# STM32F446_Supply.net
KiCad netlist of a schematic drawn in Altium Designer
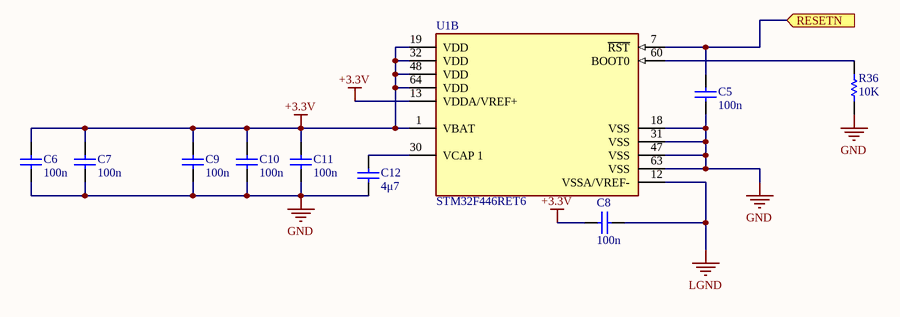
[diagram p0: STM32F446_Supply.SchDoc]

(export (version "E")
  (design (tool "Eeschema 10.0.6"))
  (components
    (comp (ref "C5")
      (value "100n")
      (footprint "CAPC0603(1608)55_N")
      (description "Keramikvielschichtkondensator, SMD, Baureihe MC, ± 10%")
      (fields (field (name "MANUFACTURER") "TDK") (field (name "TOLERANCE") "± 10%"))
      (libsource (lib "Res&Caps") (part "Cap 100n"))
    )
    (comp (ref "C6")
      (value "100n")
      (footprint "CAPC0603(1608)55_N")
      (description "Keramikvielschichtkondensator, SMD, Baureihe MC, ± 10%")
      (fields (field (name "MANUFACTURER") "TDK") (field (name "TOLERANCE") "± 10%"))
      (libsource (lib "Res&Caps") (part "Cap 100n"))
    )
    (comp (ref "C7")
      (value "100n")
      (footprint "CAPC0603(1608)55_N")
      (description "Keramikvielschichtkondensator, SMD, Baureihe MC, ± 10%")
      (fields (field (name "MANUFACTURER") "TDK") (field (name "TOLERANCE") "± 10%"))
      (libsource (lib "Res&Caps") (part "Cap 100n"))
    )
    (comp (ref "C8")
      (value "100n")
      (footprint "CAPC0603(1608)55_N")
      (description "Keramikvielschichtkondensator, SMD, Baureihe MC, ± 10%")
      (fields (field (name "MANUFACTURER") "TDK") (field (name "TOLERANCE") "± 10%"))
      (libsource (lib "Res&Caps") (part "Cap 100n"))
    )
    (comp (ref "C9")
      (value "100n")
      (footprint "CAPC0603(1608)55_N")
      (description "Keramikvielschichtkondensator, SMD, Baureihe MC, ± 10%")
      (fields (field (name "MANUFACTURER") "TDK") (field (name "TOLERANCE") "± 10%"))
      (libsource (lib "Res&Caps") (part "Cap 100n"))
    )
    (comp (ref "C10")
      (value "100n")
      (footprint "CAPC0603(1608)55_N")
      (description "Keramikvielschichtkondensator, SMD, Baureihe MC, ± 10%")
      (fields (field (name "MANUFACTURER") "TDK") (field (name "TOLERANCE") "± 10%"))
      (libsource (lib "Res&Caps") (part "Cap 100n"))
    )
    (comp (ref "C11")
      (value "100n")
      (footprint "CAPC0603(1608)55_N")
      (description "Keramikvielschichtkondensator, SMD, Baureihe MC, ± 10%")
      (fields (field (name "MANUFACTURER") "TDK") (field (name "TOLERANCE") "± 10%"))
      (libsource (lib "Res&Caps") (part "Cap 100n"))
    )
    (comp (ref "C12")
      (value "4μ7")
      (footprint "CAPC0603(1608)55_N")
      (description "Keramikvielschichtkondensator, SMD, Baureihe MC, ± 10%")
      (fields (field (name "MANUFACTURER") "TDK") (field (name "TOLERANCE") "± 10%"))
      (libsource (lib "Res&Caps") (part "Cap 4μ7"))
    )
    (comp (ref "R36")
      (value "10K")
      (footprint "RESC0603(1608)_N")
      (description "Chipwiderstand, SMD, Baureihe MC, 1%")
      (fields (field (name "MANUFACTURER") "Multicomp") (field (name "POWER") "100mW"))
      (libsource (lib "Res&Caps") (part "Res 10K"))
    )
    (comp (ref "U1")
      (value "STM32F446RET6")
      (footprint "FP-LQFP64-5W-MFG")
      (description "IC MCU 32BIT 512KB FLASH 64LQFP")
      (fields
        (field (name "OCTOPART") "https://octopart.com/stm32f446ret6-stmicroelectronics-52642920")
        (field (name "MANUFACTURER") "ST")
      )
      (libsource (lib "Altium Content Vault") (part "ee11adc32c0ab33b933cccf4348c338"))
    )
  )
  (nets
    (net (code "1") (name "+3.3V") (class "Default")
      (node (ref "C10") (pin "2") (pinfunction "2_2") (pintype "passive"))
      (node (ref "C11") (pin "2") (pinfunction "2_2") (pintype "passive"))
      (node (ref "C6") (pin "2") (pinfunction "2_2") (pintype "passive"))
      (node (ref "C7") (pin "2") (pinfunction "2_2") (pintype "passive"))
      (node (ref "C8") (pin "2") (pinfunction "2_2") (pintype "passive"))
      (node (ref "C9") (pin "2") (pinfunction "2_2") (pintype "passive"))
      (node (ref "U1") (pin "1") (pinfunction "VBAT_1") (pintype "power_in"))
      (node (ref "U1") (pin "13") (pinfunction "VDDA/VREF+_13") (pintype "power_in"))
      (node (ref "U1") (pin "19") (pinfunction "VDD_19") (pintype "power_in"))
      (node (ref "U1") (pin "32") (pinfunction "VDD_32") (pintype "power_in"))
      (node (ref "U1") (pin "48") (pinfunction "VDD_48") (pintype "power_in"))
      (node (ref "U1") (pin "64") (pinfunction "VDD_64") (pintype "power_in"))
    )
    (net (code "2") (name "/RESETN") (class "Default")
      (node (ref "C5") (pin "2") (pinfunction "2_2") (pintype "passive"))
      (node (ref "U1") (pin "7") (pinfunction "~{RST}_7") (pintype "input"))
    )
    (net (code "3") (name "GND") (class "Default")
      (node (ref "C10") (pin "1") (pinfunction "1_1") (pintype "passive"))
      (node (ref "C11") (pin "1") (pinfunction "1_1") (pintype "passive"))
      (node (ref "C12") (pin "1") (pinfunction "1_1") (pintype "passive"))
      (node (ref "C5") (pin "1") (pinfunction "1_1") (pintype "passive"))
      (node (ref "C6") (pin "1") (pinfunction "1_1") (pintype "passive"))
      (node (ref "C7") (pin "1") (pinfunction "1_1") (pintype "passive"))
      (node (ref "C9") (pin "1") (pinfunction "1_1") (pintype "passive"))
      (node (ref "R36") (pin "1") (pinfunction "1_1") (pintype "passive"))
      (node (ref "U1") (pin "18") (pinfunction "VSS_18") (pintype "power_in"))
      (node (ref "U1") (pin "31") (pinfunction "VSS_31") (pintype "power_in"))
      (node (ref "U1") (pin "47") (pinfunction "VSS_47") (pintype "power_in"))
      (node (ref "U1") (pin "63") (pinfunction "VSS_63") (pintype "power_in"))
    )
    (net (code "4") (name "LGND") (class "Default")
      (node (ref "C8") (pin "1") (pinfunction "1_1") (pintype "passive"))
      (node (ref "U1") (pin "12") (pinfunction "VSSA/VREF-_12") (pintype "power_in"))
    )
    (net (code "5") (name "Net-(U1B-BOOT0)") (class "Default")
      (node (ref "R36") (pin "2") (pinfunction "2_2") (pintype "passive"))
      (node (ref "U1") (pin "60") (pinfunction "BOOT0_60") (pintype "input"))
    )
    (net (code "6") (name "Net-(U1B-VCAP_1)") (class "Default")
      (node (ref "C12") (pin "2") (pinfunction "2_2") (pintype "passive"))
      (node (ref "U1") (pin "30") (pinfunction "VCAP_1_30") (pintype "power_in"))
    )
  )
)
